# LPDDR4.net
KiCad netlist of a schematic drawn in Altium Designer
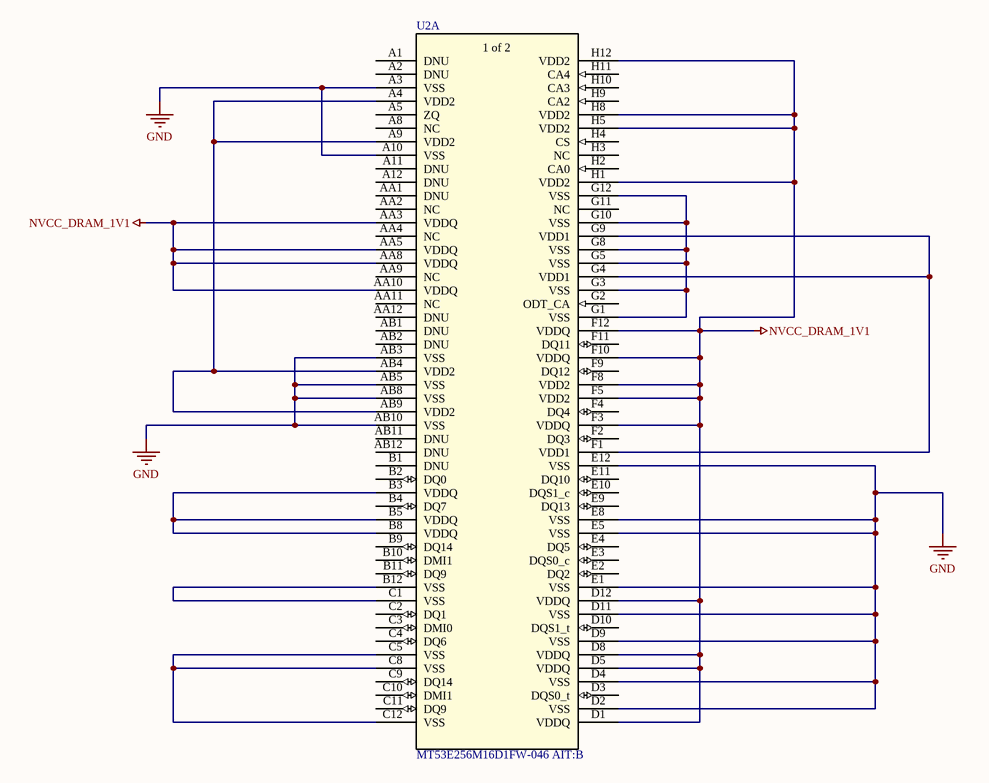
[diagram p0: LPDDR4.SchDoc]

(export (version "E")
  (design (tool "Eeschema 10.0.6"))
  (components
    (comp (ref "U2")
      (value "MT53E256M16D1FW-046 AIT:B")
      (footprint "TFBGA200_10X14p5X1p1_FW_MRN-M")
      (description "No Description Available")
      (libsource (lib "imx8mnano") (part "MT53E256M16D1FW-046 AIT{colon}B"))
    )
  )
  (nets
    (net (code "1") (name "GND") (class "Default")
      (node (ref "U2") (pin "A10") (pinfunction "VSS_A10") (pintype "power_in"))
      (node (ref "U2") (pin "A3") (pinfunction "VSS_A3") (pintype "power_in"))
      (node (ref "U2") (pin "AB10") (pinfunction "VSS_AB10") (pintype "power_in"))
      (node (ref "U2") (pin "AB3") (pinfunction "VSS_AB3") (pintype "power_in"))
      (node (ref "U2") (pin "AB5") (pinfunction "VSS_AB5") (pintype "power_in"))
      (node (ref "U2") (pin "AB8") (pinfunction "VSS_AB8") (pintype "power_in"))
      (node (ref "U2") (pin "D11") (pinfunction "VSS_D11") (pintype "power_in"))
      (node (ref "U2") (pin "D2") (pinfunction "VSS_D2") (pintype "power_in"))
      (node (ref "U2") (pin "D4") (pinfunction "VSS_D4") (pintype "power_in"))
      (node (ref "U2") (pin "D9") (pinfunction "VSS_D9") (pintype "power_in"))
      (node (ref "U2") (pin "E1") (pinfunction "VSS_E1") (pintype "power_in"))
      (node (ref "U2") (pin "E12") (pinfunction "VSS_E12") (pintype "power_in"))
      (node (ref "U2") (pin "E5") (pinfunction "VSS_E5") (pintype "power_in"))
      (node (ref "U2") (pin "E8") (pinfunction "VSS_E8") (pintype "power_in"))
    )
    (net (code "2") (name "NVCC_DRAM_1V1") (class "Default")
      (node (ref "U2") (pin "AA10") (pinfunction "VDDQ_AA10") (pintype "power_in"))
      (node (ref "U2") (pin "AA3") (pinfunction "VDDQ_AA3") (pintype "power_in"))
      (node (ref "U2") (pin "AA5") (pinfunction "VDDQ_AA5") (pintype "power_in"))
      (node (ref "U2") (pin "AA8") (pinfunction "VDDQ_AA8") (pintype "power_in"))
      (node (ref "U2") (pin "D1") (pinfunction "VDDQ_D1") (pintype "power_in"))
      (node (ref "U2") (pin "D12") (pinfunction "VDDQ_D12") (pintype "power_in"))
      (node (ref "U2") (pin "D5") (pinfunction "VDDQ_D5") (pintype "power_in"))
      (node (ref "U2") (pin "D8") (pinfunction "VDDQ_D8") (pintype "power_in"))
      (node (ref "U2") (pin "F10") (pinfunction "VDDQ_F10") (pintype "power_in"))
      (node (ref "U2") (pin "F12") (pinfunction "VDDQ_F12") (pintype "power_in"))
      (node (ref "U2") (pin "F3") (pinfunction "VDDQ_F3") (pintype "power_in"))
      (node (ref "U2") (pin "F5") (pinfunction "VDD2_F5") (pintype "power_in"))
      (node (ref "U2") (pin "F8") (pinfunction "VDD2_F8") (pintype "power_in"))
      (node (ref "U2") (pin "H1") (pinfunction "VDD2_H1") (pintype "power_in"))
      (node (ref "U2") (pin "H12") (pinfunction "VDD2_H12") (pintype "power_in"))
      (node (ref "U2") (pin "H5") (pinfunction "VDD2_H5") (pintype "power_in"))
      (node (ref "U2") (pin "H8") (pinfunction "VDD2_H8") (pintype "power_in"))
    )
    (net (code "3") (name "Net-(U2A-VDD1-PadF1)") (class "Default")
      (node (ref "U2") (pin "F1") (pinfunction "VDD1_F1") (pintype "power_in"))
      (node (ref "U2") (pin "G4") (pinfunction "VDD1_G4") (pintype "power_in"))
      (node (ref "U2") (pin "G9") (pinfunction "VDD1_G9") (pintype "power_in"))
    )
    (net (code "4") (name "Net-(U2A-VDD2-PadA4)") (class "Default")
      (node (ref "U2") (pin "A4") (pinfunction "VDD2_A4") (pintype "power_in"))
      (node (ref "U2") (pin "A9") (pinfunction "VDD2_A9") (pintype "power_in"))
      (node (ref "U2") (pin "AB4") (pinfunction "VDD2_AB4") (pintype "power_in"))
      (node (ref "U2") (pin "AB9") (pinfunction "VDD2_AB9") (pintype "power_in"))
    )
    (net (code "5") (name "Net-(U2A-VDDQ-PadB3)") (class "Default")
      (node (ref "U2") (pin "B3") (pinfunction "VDDQ_B3") (pintype "power_in"))
      (node (ref "U2") (pin "B5") (pinfunction "VDDQ_B5") (pintype "power_in"))
      (node (ref "U2") (pin "B8") (pinfunction "VDDQ_B8") (pintype "power_in"))
    )
    (net (code "6") (name "Net-(U2A-VSS-PadB12)") (class "Default")
      (node (ref "U2") (pin "B12") (pinfunction "VSS_B12") (pintype "power_in"))
      (node (ref "U2") (pin "C1") (pinfunction "VSS_C1") (pintype "power_in"))
    )
    (net (code "7") (name "Net-(U2A-VSS-PadC12)") (class "Default")
      (node (ref "U2") (pin "C12") (pinfunction "VSS_C12") (pintype "power_in"))
      (node (ref "U2") (pin "C5") (pinfunction "VSS_C5") (pintype "power_in"))
      (node (ref "U2") (pin "C8") (pinfunction "VSS_C8") (pintype "power_in"))
    )
    (net (code "8") (name "Net-(U2A-VSS-PadG1)") (class "Default")
      (node (ref "U2") (pin "G1") (pinfunction "VSS_G1") (pintype "power_in"))
      (node (ref "U2") (pin "G10") (pinfunction "VSS_G10") (pintype "power_in"))
      (node (ref "U2") (pin "G12") (pinfunction "VSS_G12") (pintype "power_in"))
      (node (ref "U2") (pin "G3") (pinfunction "VSS_G3") (pintype "power_in"))
      (node (ref "U2") (pin "G5") (pinfunction "VSS_G5") (pintype "power_in"))
      (node (ref "U2") (pin "G8") (pinfunction "VSS_G8") (pintype "power_in"))
    )
    (net (code "9") (name "unconnected-(U2A-CA0-PadH2)") (class "Default")
      (node (ref "U2") (pin "H2") (pinfunction "CA0_H2") (pintype "input"))
    )
    (net (code "10") (name "unconnected-(U2A-CA2-PadH9)") (class "Default")
      (node (ref "U2") (pin "H9") (pinfunction "CA2_H9") (pintype "input"))
    )
    (net (code "11") (name "unconnected-(U2A-CA3-PadH10)") (class "Default")
      (node (ref "U2") (pin "H10") (pinfunction "CA3_H10") (pintype "input"))
    )
    (net (code "12") (name "unconnected-(U2A-CA4-PadH11)") (class "Default")
      (node (ref "U2") (pin "H11") (pinfunction "CA4_H11") (pintype "input"))
    )
    (net (code "13") (name "unconnected-(U2A-CS-PadH4)") (class "Default")
      (node (ref "U2") (pin "H4") (pinfunction "CS_H4") (pintype "input"))
    )
    (net (code "14") (name "unconnected-(U2A-DMI0-PadC3)") (class "Default")
      (node (ref "U2") (pin "C3") (pinfunction "DMI0_C3") (pintype "bidirectional"))
    )
    (net (code "15") (name "unconnected-(U2A-DMI1-PadB10)") (class "Default")
      (node (ref "U2") (pin "B10") (pinfunction "DMI1_B10") (pintype "bidirectional"))
    )
    (net (code "16") (name "unconnected-(U2A-DMI1-PadC10)") (class "Default")
      (node (ref "U2") (pin "C10") (pinfunction "DMI1_C10") (pintype "bidirectional"))
    )
    (net (code "17") (name "unconnected-(U2A-DNU-PadA1)") (class "Default")
      (node (ref "U2") (pin "A1") (pinfunction "DNU_A1") (pintype "passive"))
    )
    (net (code "18") (name "unconnected-(U2A-DNU-PadA2)") (class "Default")
      (node (ref "U2") (pin "A2") (pinfunction "DNU_A2") (pintype "passive"))
    )
    (net (code "19") (name "unconnected-(U2A-DNU-PadA11)") (class "Default")
      (node (ref "U2") (pin "A11") (pinfunction "DNU_A11") (pintype "passive"))
    )
    (net (code "20") (name "unconnected-(U2A-DNU-PadA12)") (class "Default")
      (node (ref "U2") (pin "A12") (pinfunction "DNU_A12") (pintype "passive"))
    )
    (net (code "21") (name "unconnected-(U2A-DNU-PadAA1)") (class "Default")
      (node (ref "U2") (pin "AA1") (pinfunction "DNU_AA1") (pintype "passive"))
    )
    (net (code "22") (name "unconnected-(U2A-DNU-PadAA12)") (class "Default")
      (node (ref "U2") (pin "AA12") (pinfunction "DNU_AA12") (pintype "passive"))
    )
    (net (code "23") (name "unconnected-(U2A-DNU-PadAB1)") (class "Default")
      (node (ref "U2") (pin "AB1") (pinfunction "DNU_AB1") (pintype "passive"))
    )
    (net (code "24") (name "unconnected-(U2A-DNU-PadAB2)") (class "Default")
      (node (ref "U2") (pin "AB2") (pinfunction "DNU_AB2") (pintype "passive"))
    )
    (net (code "25") (name "unconnected-(U2A-DNU-PadAB11)") (class "Default")
      (node (ref "U2") (pin "AB11") (pinfunction "DNU_AB11") (pintype "passive"))
    )
    (net (code "26") (name "unconnected-(U2A-DNU-PadAB12)") (class "Default")
      (node (ref "U2") (pin "AB12") (pinfunction "DNU_AB12") (pintype "passive"))
    )
    (net (code "27") (name "unconnected-(U2A-DNU-PadB1)") (class "Default")
      (node (ref "U2") (pin "B1") (pinfunction "DNU_B1") (pintype "passive"))
    )
    (net (code "28") (name "unconnected-(U2A-DQ0-PadB2)") (class "Default")
      (node (ref "U2") (pin "B2") (pinfunction "DQ0_B2") (pintype "bidirectional"))
    )
    (net (code "29") (name "unconnected-(U2A-DQ1-PadC2)") (class "Default")
      (node (ref "U2") (pin "C2") (pinfunction "DQ1_C2") (pintype "bidirectional"))
    )
    (net (code "30") (name "unconnected-(U2A-DQ2-PadE2)") (class "Default")
      (node (ref "U2") (pin "E2") (pinfunction "DQ2_E2") (pintype "bidirectional"))
    )
    (net (code "31") (name "unconnected-(U2A-DQ3-PadF2)") (class "Default")
      (node (ref "U2") (pin "F2") (pinfunction "DQ3_F2") (pintype "bidirectional"))
    )
    (net (code "32") (name "unconnected-(U2A-DQ4-PadF4)") (class "Default")
      (node (ref "U2") (pin "F4") (pinfunction "DQ4_F4") (pintype "bidirectional"))
    )
    (net (code "33") (name "unconnected-(U2A-DQ5-PadE4)") (class "Default")
      (node (ref "U2") (pin "E4") (pinfunction "DQ5_E4") (pintype "bidirectional"))
    )
    (net (code "34") (name "unconnected-(U2A-DQ6-PadC4)") (class "Default")
      (node (ref "U2") (pin "C4") (pinfunction "DQ6_C4") (pintype "bidirectional"))
    )
    (net (code "35") (name "unconnected-(U2A-DQ7-PadB4)") (class "Default")
      (node (ref "U2") (pin "B4") (pinfunction "DQ7_B4") (pintype "bidirectional"))
    )
    (net (code "36") (name "unconnected-(U2A-DQ9-PadB11)") (class "Default")
      (node (ref "U2") (pin "B11") (pinfunction "DQ9_B11") (pintype "bidirectional"))
    )
    (net (code "37") (name "unconnected-(U2A-DQ9-PadC11)") (class "Default")
      (node (ref "U2") (pin "C11") (pinfunction "DQ9_C11") (pintype "bidirectional"))
    )
    (net (code "38") (name "unconnected-(U2A-DQ10-PadE11)") (class "Default")
      (node (ref "U2") (pin "E11") (pinfunction "DQ10_E11") (pintype "bidirectional"))
    )
    (net (code "39") (name "unconnected-(U2A-DQ11-PadF11)") (class "Default")
      (node (ref "U2") (pin "F11") (pinfunction "DQ11_F11") (pintype "bidirectional"))
    )
    (net (code "40") (name "unconnected-(U2A-DQ12-PadF9)") (class "Default")
      (node (ref "U2") (pin "F9") (pinfunction "DQ12_F9") (pintype "bidirectional"))
    )
    (net (code "41") (name "unconnected-(U2A-DQ13-PadE9)") (class "Default")
      (node (ref "U2") (pin "E9") (pinfunction "DQ13_E9") (pintype "bidirectional"))
    )
    (net (code "42") (name "unconnected-(U2A-DQ14-PadB9)") (class "Default")
      (node (ref "U2") (pin "B9") (pinfunction "DQ14_B9") (pintype "bidirectional"))
    )
    (net (code "43") (name "unconnected-(U2A-DQ14-PadC9)") (class "Default")
      (node (ref "U2") (pin "C9") (pinfunction "DQ14_C9") (pintype "bidirectional"))
    )
    (net (code "44") (name "unconnected-(U2A-DQS0_c-PadE3)") (class "Default")
      (node (ref "U2") (pin "E3") (pinfunction "DQS0_c_E3") (pintype "bidirectional"))
    )
    (net (code "45") (name "unconnected-(U2A-DQS0_t-PadD3)") (class "Default")
      (node (ref "U2") (pin "D3") (pinfunction "DQS0_t_D3") (pintype "bidirectional"))
    )
    (net (code "46") (name "unconnected-(U2A-DQS1_c-PadE10)") (class "Default")
      (node (ref "U2") (pin "E10") (pinfunction "DQS1_c_E10") (pintype "bidirectional"))
    )
    (net (code "47") (name "unconnected-(U2A-DQS1_t-PadD10)") (class "Default")
      (node (ref "U2") (pin "D10") (pinfunction "DQS1_t_D10") (pintype "bidirectional"))
    )
    (net (code "48") (name "unconnected-(U2A-NC-PadA8)") (class "Default")
      (node (ref "U2") (pin "A8") (pinfunction "NC_A8") (pintype "passive"))
    )
    (net (code "49") (name "unconnected-(U2A-NC-PadAA2)") (class "Default")
      (node (ref "U2") (pin "AA2") (pinfunction "NC_AA2") (pintype "passive"))
    )
    (net (code "50") (name "unconnected-(U2A-NC-PadAA4)") (class "Default")
      (node (ref "U2") (pin "AA4") (pinfunction "NC_AA4") (pintype "passive"))
    )
    (net (code "51") (name "unconnected-(U2A-NC-PadAA9)") (class "Default")
      (node (ref "U2") (pin "AA9") (pinfunction "NC_AA9") (pintype "passive"))
    )
    (net (code "52") (name "unconnected-(U2A-NC-PadAA11)") (class "Default")
      (node (ref "U2") (pin "AA11") (pinfunction "NC_AA11") (pintype "passive"))
    )
    (net (code "53") (name "unconnected-(U2A-NC-PadG11)") (class "Default")
      (node (ref "U2") (pin "G11") (pinfunction "NC_G11") (pintype "passive"))
    )
    (net (code "54") (name "unconnected-(U2A-NC-PadH3)") (class "Default")
      (node (ref "U2") (pin "H3") (pinfunction "NC_H3") (pintype "passive"))
    )
    (net (code "55") (name "unconnected-(U2A-ODT_CA-PadG2)") (class "Default")
      (node (ref "U2") (pin "G2") (pinfunction "ODT_CA_G2") (pintype "input"))
    )
    (net (code "56") (name "unconnected-(U2A-ZQ-PadA5)") (class "Default")
      (node (ref "U2") (pin "A5") (pinfunction "ZQ_A5") (pintype "power_in"))
    )
  )
)
